# OneSLiPoCharger.net
KiCad netlist of a schematic drawn in EAGLE
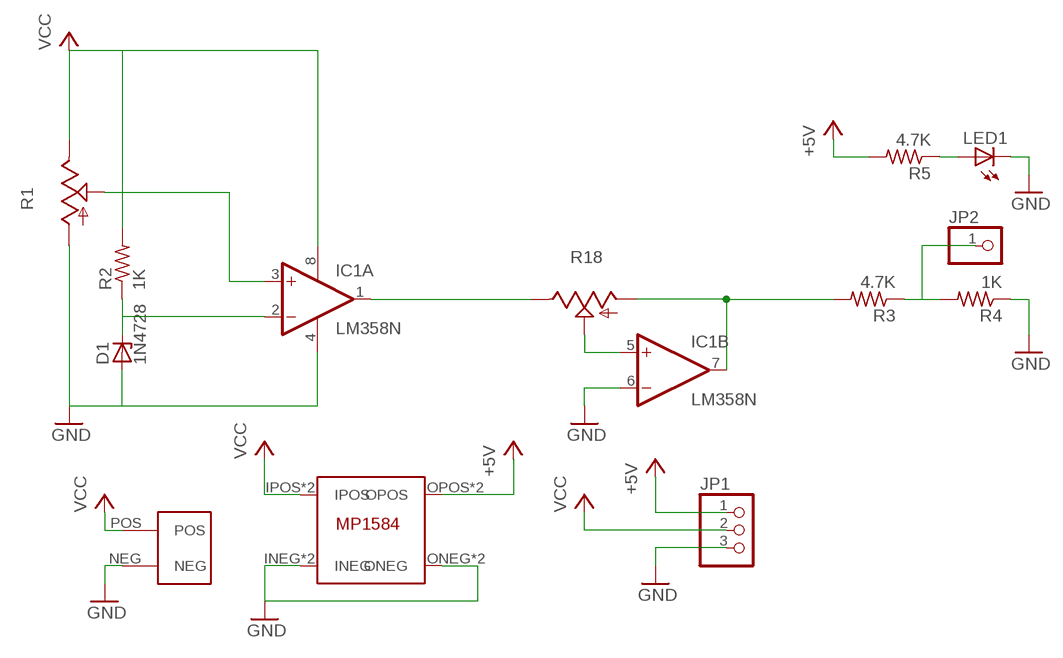
[diagram p0: schematic, sheet 1]
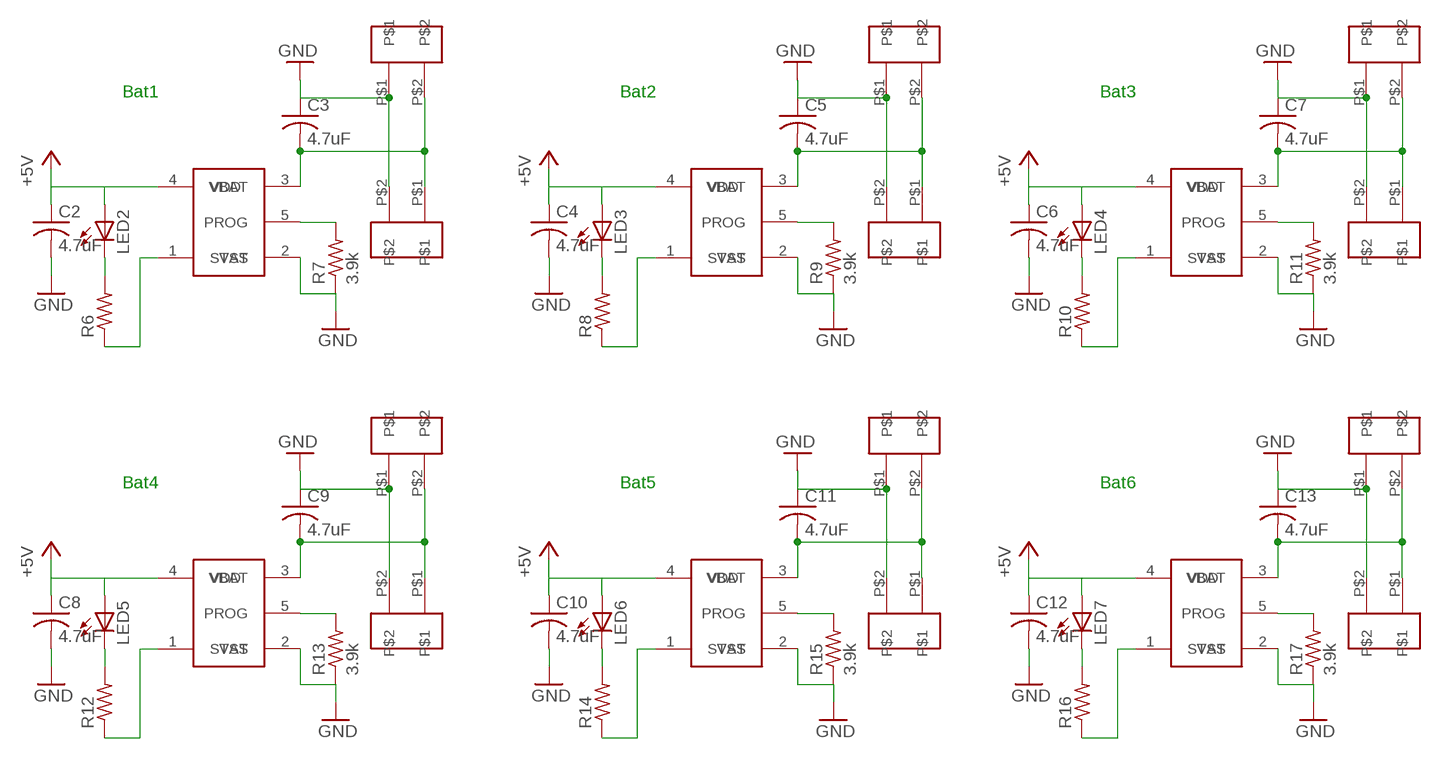
[diagram p1: schematic, sheet 2]

(export (version "E")
  (design (tool "Eeschema 10.0.6"))
  (components
    (comp (ref "C2")
      (value "4.7uF")
      (footprint "eagle-import:C0805")
      (libsource (lib "eagle-import") (part "C-USC0805"))
    )
    (comp (ref "C3")
      (value "4.7uF")
      (footprint "eagle-import:C0805")
      (libsource (lib "eagle-import") (part "C-USC0805"))
    )
    (comp (ref "C4")
      (value "4.7uF")
      (footprint "eagle-import:C0805")
      (libsource (lib "eagle-import") (part "C-USC0805"))
    )
    (comp (ref "C5")
      (value "4.7uF")
      (footprint "eagle-import:C0805")
      (libsource (lib "eagle-import") (part "C-USC0805"))
    )
    (comp (ref "C6")
      (value "4.7uF")
      (footprint "eagle-import:C0805")
      (libsource (lib "eagle-import") (part "C-USC0805"))
    )
    (comp (ref "C7")
      (value "4.7uF")
      (footprint "eagle-import:C0805")
      (libsource (lib "eagle-import") (part "C-USC0805"))
    )
    (comp (ref "C8")
      (value "4.7uF")
      (footprint "eagle-import:C0805")
      (libsource (lib "eagle-import") (part "C-USC0805"))
    )
    (comp (ref "C9")
      (value "4.7uF")
      (footprint "eagle-import:C0805")
      (libsource (lib "eagle-import") (part "C-USC0805"))
    )
    (comp (ref "C10")
      (value "4.7uF")
      (footprint "eagle-import:C0805")
      (libsource (lib "eagle-import") (part "C-USC0805"))
    )
    (comp (ref "C11")
      (value "4.7uF")
      (footprint "eagle-import:C0805")
      (libsource (lib "eagle-import") (part "C-USC0805"))
    )
    (comp (ref "C12")
      (value "4.7uF")
      (footprint "eagle-import:C0805")
      (libsource (lib "eagle-import") (part "C-USC0805"))
    )
    (comp (ref "C13")
      (value "4.7uF")
      (footprint "eagle-import:C0805")
      (libsource (lib "eagle-import") (part "C-USC0805"))
    )
    (comp (ref "LED2")
      (value "LED3MM")
      (footprint "eagle-import:LED3MM")
      (libsource (lib "eagle-import") (part "LED3MM"))
    )
    (comp (ref "LED3")
      (value "LED3MM")
      (footprint "eagle-import:LED3MM")
      (libsource (lib "eagle-import") (part "LED3MM"))
    )
    (comp (ref "LED4")
      (value "LED3MM")
      (footprint "eagle-import:LED3MM")
      (libsource (lib "eagle-import") (part "LED3MM"))
    )
    (comp (ref "LED5")
      (value "LED3MM")
      (footprint "eagle-import:LED3MM")
      (libsource (lib "eagle-import") (part "LED3MM"))
    )
    (comp (ref "LED6")
      (value "LED3MM")
      (footprint "eagle-import:LED3MM")
      (libsource (lib "eagle-import") (part "LED3MM"))
    )
    (comp (ref "LED7")
      (value "LED3MM")
      (footprint "eagle-import:LED3MM")
      (libsource (lib "eagle-import") (part "LED3MM"))
    )
    (comp (ref "R6")
      (value "R-US_M0805")
      (footprint "eagle-import:M0805")
      (libsource (lib "eagle-import") (part "R-US_M0805"))
    )
    (comp (ref "R7")
      (value "3.9k")
      (footprint "eagle-import:M0805")
      (libsource (lib "eagle-import") (part "R-US_M0805"))
    )
    (comp (ref "R8")
      (value "R-US_M0805")
      (footprint "eagle-import:M0805")
      (libsource (lib "eagle-import") (part "R-US_M0805"))
    )
    (comp (ref "R9")
      (value "3.9k")
      (footprint "eagle-import:M0805")
      (libsource (lib "eagle-import") (part "R-US_M0805"))
    )
    (comp (ref "R10")
      (value "R-US_M0805")
      (footprint "eagle-import:M0805")
      (libsource (lib "eagle-import") (part "R-US_M0805"))
    )
    (comp (ref "R11")
      (value "3.9k")
      (footprint "eagle-import:M0805")
      (libsource (lib "eagle-import") (part "R-US_M0805"))
    )
    (comp (ref "R12")
      (value "R-US_M0805")
      (footprint "eagle-import:M0805")
      (libsource (lib "eagle-import") (part "R-US_M0805"))
    )
    (comp (ref "R13")
      (value "3.9k")
      (footprint "eagle-import:M0805")
      (libsource (lib "eagle-import") (part "R-US_M0805"))
    )
    (comp (ref "R14")
      (value "R-US_M0805")
      (footprint "eagle-import:M0805")
      (libsource (lib "eagle-import") (part "R-US_M0805"))
    )
    (comp (ref "R15")
      (value "3.9k")
      (footprint "eagle-import:M0805")
      (libsource (lib "eagle-import") (part "R-US_M0805"))
    )
    (comp (ref "R16")
      (value "R-US_M0805")
      (footprint "eagle-import:M0805")
      (libsource (lib "eagle-import") (part "R-US_M0805"))
    )
    (comp (ref "R17")
      (value "3.9k")
      (footprint "eagle-import:M0805")
      (libsource (lib "eagle-import") (part "R-US_M0805"))
    )
    (comp (ref "U$1")
      (value "MCP73831")
      (footprint "eagle-import:MCP73831-SOT23")
      (libsource (lib "eagle-import") (part "MCP73831"))
    )
    (comp (ref "U$2")
      (value "PICOBLADE-2PIN")
      (footprint "eagle-import:PICOBLADE-2PIN")
      (libsource (lib "eagle-import") (part "PICOBLADE-2PIN"))
    )
    (comp (ref "U$4")
      (value "MCP73831")
      (footprint "eagle-import:MCP73831-SOT23")
      (libsource (lib "eagle-import") (part "MCP73831"))
    )
    (comp (ref "U$5")
      (value "PICOBLADE-2PIN")
      (footprint "eagle-import:PICOBLADE-2PIN")
      (libsource (lib "eagle-import") (part "PICOBLADE-2PIN"))
    )
    (comp (ref "U$6")
      (value "MCP73831")
      (footprint "eagle-import:MCP73831-SOT23")
      (libsource (lib "eagle-import") (part "MCP73831"))
    )
    (comp (ref "U$7")
      (value "PICOBLADE-2PIN")
      (footprint "eagle-import:PICOBLADE-2PIN")
      (libsource (lib "eagle-import") (part "PICOBLADE-2PIN"))
    )
    (comp (ref "U$8")
      (value "MCP73831")
      (footprint "eagle-import:MCP73831-SOT23")
      (libsource (lib "eagle-import") (part "MCP73831"))
    )
    (comp (ref "U$9")
      (value "PICOBLADE-2PIN")
      (footprint "eagle-import:PICOBLADE-2PIN")
      (libsource (lib "eagle-import") (part "PICOBLADE-2PIN"))
    )
    (comp (ref "U$10")
      (value "MCP73831")
      (footprint "eagle-import:MCP73831-SOT23")
      (libsource (lib "eagle-import") (part "MCP73831"))
    )
    (comp (ref "U$11")
      (value "PICOBLADE-2PIN")
      (footprint "eagle-import:PICOBLADE-2PIN")
      (libsource (lib "eagle-import") (part "PICOBLADE-2PIN"))
    )
    (comp (ref "U$12")
      (value "MCP73831")
      (footprint "eagle-import:MCP73831-SOT23")
      (libsource (lib "eagle-import") (part "MCP73831"))
    )
    (comp (ref "U$13")
      (value "PICOBLADE-2PIN")
      (footprint "eagle-import:PICOBLADE-2PIN")
      (libsource (lib "eagle-import") (part "PICOBLADE-2PIN"))
    )
    (comp (ref "U$15")
      (value "JST-PH-2POS")
      (footprint "eagle-import:JST-PH-2POS")
      (libsource (lib "eagle-import") (part "JST-PH-2POS"))
    )
    (comp (ref "U$16")
      (value "JST-PH-2POS")
      (footprint "eagle-import:JST-PH-2POS")
      (libsource (lib "eagle-import") (part "JST-PH-2POS"))
    )
    (comp (ref "U$17")
      (value "JST-PH-2POS")
      (footprint "eagle-import:JST-PH-2POS")
      (libsource (lib "eagle-import") (part "JST-PH-2POS"))
    )
    (comp (ref "U$18")
      (value "JST-PH-2POS")
      (footprint "eagle-import:JST-PH-2POS")
      (libsource (lib "eagle-import") (part "JST-PH-2POS"))
    )
    (comp (ref "U$19")
      (value "JST-PH-2POS")
      (footprint "eagle-import:JST-PH-2POS")
      (libsource (lib "eagle-import") (part "JST-PH-2POS"))
    )
    (comp (ref "U$20")
      (value "JST-PH-2POS")
      (footprint "eagle-import:JST-PH-2POS")
      (libsource (lib "eagle-import") (part "JST-PH-2POS"))
    )
    (comp (ref "D1")
      (value "1N4728")
      (footprint "eagle-import:DO41Z10")
      (libsource (lib "eagle-import") (part "1N4728"))
    )
    (comp (ref "IC1")
      (value "LM358N")
      (footprint "eagle-import:DIL08")
      (libsource (lib "eagle-import") (part "LM358N"))
    )
    (comp (ref "JP1")
      (value "PINHD-1X3")
      (footprint "eagle-import:1X03")
      (libsource (lib "eagle-import") (part "PINHD-1X3"))
    )
    (comp (ref "JP2")
      (value "PINHD-1X1")
      (footprint "eagle-import:1X01")
      (libsource (lib "eagle-import") (part "PINHD-1X1"))
    )
    (comp (ref "LED1")
      (value "LED3MM")
      (footprint "eagle-import:LED3MM")
      (libsource (lib "eagle-import") (part "LED3MM"))
    )
    (comp (ref "R1")
      (value "TRIM_US-B25P")
      (footprint "eagle-import:B25P")
      (libsource (lib "eagle-import") (part "TRIM_US-B25P"))
    )
    (comp (ref "R2")
      (value "1K")
      (footprint "eagle-import:0207_10")
      (libsource (lib "eagle-import") (part "R-US_0207/10"))
    )
    (comp (ref "R3")
      (value "4.7K")
      (footprint "eagle-import:0207_10")
      (libsource (lib "eagle-import") (part "R-US_0207/10"))
    )
    (comp (ref "R4")
      (value "1K")
      (footprint "eagle-import:0207_10")
      (libsource (lib "eagle-import") (part "R-US_0207/10"))
    )
    (comp (ref "R5")
      (value "4.7K")
      (footprint "eagle-import:0207_10")
      (libsource (lib "eagle-import") (part "R-US_0207/10"))
    )
    (comp (ref "R18")
      (value "TRIM_US-B25P")
      (footprint "eagle-import:B25P")
      (libsource (lib "eagle-import") (part "TRIM_US-B25P"))
    )
    (comp (ref "U$3")
      (value "XT60")
      (footprint "eagle-import:XT60")
      (libsource (lib "eagle-import") (part "XT60"))
    )
    (comp (ref "U$14")
      (value "MP1584EN-MOD")
      (footprint "eagle-import:MP1584MOD-TH")
      (libsource (lib "eagle-import") (part "MP1584EN-MOD"))
    )
  )
  (nets
    (net (code "1") (name "+5V") (class "Default")
      (node (ref "C10") (pin "1") (pinfunction "1_1") (pintype "passive"))
      (node (ref "C12") (pin "1") (pinfunction "1_1") (pintype "passive"))
      (node (ref "C2") (pin "1") (pinfunction "1_1") (pintype "passive"))
      (node (ref "C4") (pin "1") (pinfunction "1_1") (pintype "passive"))
      (node (ref "C6") (pin "1") (pinfunction "1_1") (pintype "passive"))
      (node (ref "C8") (pin "1") (pinfunction "1_1") (pintype "passive"))
      (node (ref "JP1") (pin "1") (pinfunction "1_1") (pintype "passive"))
      (node (ref "LED2") (pin "A") (pinfunction "A_A") (pintype "passive"))
      (node (ref "LED3") (pin "A") (pinfunction "A_A") (pintype "passive"))
      (node (ref "LED4") (pin "A") (pinfunction "A_A") (pintype "passive"))
      (node (ref "LED5") (pin "A") (pinfunction "A_A") (pintype "passive"))
      (node (ref "LED6") (pin "A") (pinfunction "A_A") (pintype "passive"))
      (node (ref "LED7") (pin "A") (pinfunction "A_A") (pintype "passive"))
      (node (ref "R5") (pin "2") (pinfunction "2_2") (pintype "passive"))
      (node (ref "U$1") (pin "4") (pinfunction "VDD_4") (pintype "bidirectional"))
      (node (ref "U$10") (pin "4") (pinfunction "VDD_4") (pintype "bidirectional"))
      (node (ref "U$12") (pin "4") (pinfunction "VDD_4") (pintype "bidirectional"))
      (node (ref "U$14") (pin "OPOS") (pinfunction "OPOS_OPOS") (pintype "bidirectional"))
      (node (ref "U$14") (pin "OPOS1") (pinfunction "OPOS_OPOS1") (pintype "bidirectional"))
      (node (ref "U$4") (pin "4") (pinfunction "VDD_4") (pintype "bidirectional"))
      (node (ref "U$6") (pin "4") (pinfunction "VDD_4") (pintype "bidirectional"))
      (node (ref "U$8") (pin "4") (pinfunction "VDD_4") (pintype "bidirectional"))
    )
    (net (code "2") (name "GND") (class "Default")
      (node (ref "C10") (pin "2") (pinfunction "2_2") (pintype "passive"))
      (node (ref "C11") (pin "1") (pinfunction "1_1") (pintype "passive"))
      (node (ref "C12") (pin "2") (pinfunction "2_2") (pintype "passive"))
      (node (ref "C13") (pin "1") (pinfunction "1_1") (pintype "passive"))
      (node (ref "C2") (pin "2") (pinfunction "2_2") (pintype "passive"))
      (node (ref "C3") (pin "1") (pinfunction "1_1") (pintype "passive"))
      (node (ref "C4") (pin "2") (pinfunction "2_2") (pintype "passive"))
      (node (ref "C5") (pin "1") (pinfunction "1_1") (pintype "passive"))
      (node (ref "C6") (pin "2") (pinfunction "2_2") (pintype "passive"))
      (node (ref "C7") (pin "1") (pinfunction "1_1") (pintype "passive"))
      (node (ref "C8") (pin "2") (pinfunction "2_2") (pintype "passive"))
      (node (ref "C9") (pin "1") (pinfunction "1_1") (pintype "passive"))
      (node (ref "D1") (pin "A") (pinfunction "A_A") (pintype "passive"))
      (node (ref "IC1") (pin "4") (pinfunction "V-_4") (pintype "power_in"))
      (node (ref "IC1") (pin "6") (pinfunction "-IN_6") (pintype "input"))
      (node (ref "JP1") (pin "3") (pinfunction "3_3") (pintype "passive"))
      (node (ref "LED1") (pin "K") (pinfunction "C_K") (pintype "passive"))
      (node (ref "R1") (pin "A") (pinfunction "A_A") (pintype "passive"))
      (node (ref "R11") (pin "1") (pinfunction "1_1") (pintype "passive"))
      (node (ref "R13") (pin "1") (pinfunction "1_1") (pintype "passive"))
      (node (ref "R15") (pin "1") (pinfunction "1_1") (pintype "passive"))
      (node (ref "R17") (pin "1") (pinfunction "1_1") (pintype "passive"))
      (node (ref "R4") (pin "1") (pinfunction "1_1") (pintype "passive"))
      (node (ref "R7") (pin "1") (pinfunction "1_1") (pintype "passive"))
      (node (ref "R9") (pin "1") (pinfunction "1_1") (pintype "passive"))
      (node (ref "U$1") (pin "2") (pinfunction "VSS_2") (pintype "bidirectional"))
      (node (ref "U$10") (pin "2") (pinfunction "VSS_2") (pintype "bidirectional"))
      (node (ref "U$11") (pin "P$1") (pinfunction "P$1_P$1") (pintype "bidirectional"))
      (node (ref "U$12") (pin "2") (pinfunction "VSS_2") (pintype "bidirectional"))
      (node (ref "U$13") (pin "P$1") (pinfunction "P$1_P$1") (pintype "bidirectional"))
      (node (ref "U$14") (pin "INEG") (pinfunction "INEG_INEG") (pintype "bidirectional"))
      (node (ref "U$14") (pin "INEG1") (pinfunction "INEG_INEG1") (pintype "bidirectional"))
      (node (ref "U$14") (pin "ONEG") (pinfunction "ONEG_ONEG") (pintype "bidirectional"))
      (node (ref "U$14") (pin "ONEG1") (pinfunction "ONEG_ONEG1") (pintype "bidirectional"))
      (node (ref "U$15") (pin "P$2") (pinfunction "P$2_P$2") (pintype "bidirectional"))
      (node (ref "U$16") (pin "P$2") (pinfunction "P$2_P$2") (pintype "bidirectional"))
      (node (ref "U$17") (pin "P$2") (pinfunction "P$2_P$2") (pintype "bidirectional"))
      (node (ref "U$18") (pin "P$2") (pinfunction "P$2_P$2") (pintype "bidirectional"))
      (node (ref "U$19") (pin "P$2") (pinfunction "P$2_P$2") (pintype "bidirectional"))
      (node (ref "U$2") (pin "P$1") (pinfunction "P$1_P$1") (pintype "bidirectional"))
      (node (ref "U$20") (pin "P$2") (pinfunction "P$2_P$2") (pintype "bidirectional"))
      (node (ref "U$3") (pin "NEG") (pinfunction "NEG_NEG") (pintype "bidirectional"))
      (node (ref "U$4") (pin "2") (pinfunction "VSS_2") (pintype "bidirectional"))
      (node (ref "U$5") (pin "P$1") (pinfunction "P$1_P$1") (pintype "bidirectional"))
      (node (ref "U$6") (pin "2") (pinfunction "VSS_2") (pintype "bidirectional"))
      (node (ref "U$7") (pin "P$1") (pinfunction "P$1_P$1") (pintype "bidirectional"))
      (node (ref "U$8") (pin "2") (pinfunction "VSS_2") (pintype "bidirectional"))
      (node (ref "U$9") (pin "P$1") (pinfunction "P$1_P$1") (pintype "bidirectional"))
    )
    (net (code "3") (name "Net-(IC1A-+IN)") (class "Default")
      (node (ref "IC1") (pin "3") (pinfunction "+IN_3") (pintype "input"))
      (node (ref "R1") (pin "S") (pinfunction "S_S") (pintype "passive"))
    )
    (net (code "4") (name "Net-(IC1A--IN)") (class "Default")
      (node (ref "D1") (pin "C") (pinfunction "C_C") (pintype "passive"))
      (node (ref "IC1") (pin "2") (pinfunction "-IN_2") (pintype "input"))
      (node (ref "R2") (pin "1") (pinfunction "1_1") (pintype "passive"))
    )
    (net (code "5") (name "Net-(IC1A-OUT)") (class "Default")
      (node (ref "IC1") (pin "1") (pinfunction "OUT_1") (pintype "output"))
      (node (ref "R18") (pin "E") (pinfunction "E_E") (pintype "passive"))
    )
    (net (code "6") (name "Net-(IC1B-+IN)") (class "Default")
      (node (ref "IC1") (pin "5") (pinfunction "+IN_5") (pintype "input"))
      (node (ref "R18") (pin "S") (pinfunction "S_S") (pintype "passive"))
    )
    (net (code "7") (name "Net-(IC1B-OUT)") (class "Default")
      (node (ref "IC1") (pin "7") (pinfunction "OUT_7") (pintype "output"))
      (node (ref "R18") (pin "A") (pinfunction "A_A") (pintype "passive"))
      (node (ref "R3") (pin "2") (pinfunction "2_2") (pintype "passive"))
    )
    (net (code "8") (name "Net-(JP2-Pad1)") (class "Default")
      (node (ref "JP2") (pin "1") (pinfunction "1_1") (pintype "passive"))
      (node (ref "R3") (pin "1") (pinfunction "1_1") (pintype "passive"))
      (node (ref "R4") (pin "2") (pinfunction "2_2") (pintype "passive"))
    )
    (net (code "9") (name "Net-(LED1-PadA)") (class "Default")
      (node (ref "LED1") (pin "A") (pinfunction "A_A") (pintype "passive"))
      (node (ref "R5") (pin "1") (pinfunction "1_1") (pintype "passive"))
    )
    (net (code "10") (name "Net-(LED2-C)") (class "Default")
      (node (ref "LED2") (pin "K") (pinfunction "C_K") (pintype "passive"))
      (node (ref "R6") (pin "2") (pinfunction "2_2") (pintype "passive"))
    )
    (net (code "11") (name "Net-(LED3-C)") (class "Default")
      (node (ref "LED3") (pin "K") (pinfunction "C_K") (pintype "passive"))
      (node (ref "R8") (pin "2") (pinfunction "2_2") (pintype "passive"))
    )
    (net (code "12") (name "Net-(LED4-C)") (class "Default")
      (node (ref "LED4") (pin "K") (pinfunction "C_K") (pintype "passive"))
      (node (ref "R10") (pin "2") (pinfunction "2_2") (pintype "passive"))
    )
    (net (code "13") (name "Net-(LED5-C)") (class "Default")
      (node (ref "LED5") (pin "K") (pinfunction "C_K") (pintype "passive"))
      (node (ref "R12") (pin "2") (pinfunction "2_2") (pintype "passive"))
    )
    (net (code "14") (name "Net-(LED6-C)") (class "Default")
      (node (ref "LED6") (pin "K") (pinfunction "C_K") (pintype "passive"))
      (node (ref "R14") (pin "2") (pinfunction "2_2") (pintype "passive"))
    )
    (net (code "15") (name "Net-(LED7-C)") (class "Default")
      (node (ref "LED7") (pin "K") (pinfunction "C_K") (pintype "passive"))
      (node (ref "R16") (pin "2") (pinfunction "2_2") (pintype "passive"))
    )
    (net (code "16") (name "Net-(U$1-PROG)") (class "Default")
      (node (ref "R7") (pin "2") (pinfunction "2_2") (pintype "passive"))
      (node (ref "U$1") (pin "5") (pinfunction "PROG_5") (pintype "bidirectional"))
    )
    (net (code "17") (name "Net-(U$1-STAT)") (class "Default")
      (node (ref "R6") (pin "1") (pinfunction "1_1") (pintype "passive"))
      (node (ref "U$1") (pin "1") (pinfunction "STAT_1") (pintype "bidirectional"))
    )
    (net (code "18") (name "Net-(U$1-VBAT)") (class "Default")
      (node (ref "C3") (pin "2") (pinfunction "2_2") (pintype "passive"))
      (node (ref "U$1") (pin "3") (pinfunction "VBAT_3") (pintype "bidirectional"))
      (node (ref "U$15") (pin "P$1") (pinfunction "P$1_P$1") (pintype "bidirectional"))
      (node (ref "U$2") (pin "P$2") (pinfunction "P$2_P$2") (pintype "bidirectional"))
    )
    (net (code "19") (name "Net-(U$4-PROG)") (class "Default")
      (node (ref "R9") (pin "2") (pinfunction "2_2") (pintype "passive"))
      (node (ref "U$4") (pin "5") (pinfunction "PROG_5") (pintype "bidirectional"))
    )
    (net (code "20") (name "Net-(U$4-STAT)") (class "Default")
      (node (ref "R8") (pin "1") (pinfunction "1_1") (pintype "passive"))
      (node (ref "U$4") (pin "1") (pinfunction "STAT_1") (pintype "bidirectional"))
    )
    (net (code "21") (name "Net-(U$4-VBAT)") (class "Default")
      (node (ref "C5") (pin "2") (pinfunction "2_2") (pintype "passive"))
      (node (ref "U$16") (pin "P$1") (pinfunction "P$1_P$1") (pintype "bidirectional"))
      (node (ref "U$4") (pin "3") (pinfunction "VBAT_3") (pintype "bidirectional"))
      (node (ref "U$5") (pin "P$2") (pinfunction "P$2_P$2") (pintype "bidirectional"))
    )
    (net (code "22") (name "Net-(U$6-PROG)") (class "Default")
      (node (ref "R11") (pin "2") (pinfunction "2_2") (pintype "passive"))
      (node (ref "U$6") (pin "5") (pinfunction "PROG_5") (pintype "bidirectional"))
    )
    (net (code "23") (name "Net-(U$6-STAT)") (class "Default")
      (node (ref "R10") (pin "1") (pinfunction "1_1") (pintype "passive"))
      (node (ref "U$6") (pin "1") (pinfunction "STAT_1") (pintype "bidirectional"))
    )
    (net (code "24") (name "Net-(U$6-VBAT)") (class "Default")
      (node (ref "C7") (pin "2") (pinfunction "2_2") (pintype "passive"))
      (node (ref "U$17") (pin "P$1") (pinfunction "P$1_P$1") (pintype "bidirectional"))
      (node (ref "U$6") (pin "3") (pinfunction "VBAT_3") (pintype "bidirectional"))
      (node (ref "U$7") (pin "P$2") (pinfunction "P$2_P$2") (pintype "bidirectional"))
    )
    (net (code "25") (name "Net-(U$8-PROG)") (class "Default")
      (node (ref "R13") (pin "2") (pinfunction "2_2") (pintype "passive"))
      (node (ref "U$8") (pin "5") (pinfunction "PROG_5") (pintype "bidirectional"))
    )
    (net (code "26") (name "Net-(U$8-STAT)") (class "Default")
      (node (ref "R12") (pin "1") (pinfunction "1_1") (pintype "passive"))
      (node (ref "U$8") (pin "1") (pinfunction "STAT_1") (pintype "bidirectional"))
    )
    (net (code "27") (name "Net-(U$8-VBAT)") (class "Default")
      (node (ref "C9") (pin "2") (pinfunction "2_2") (pintype "passive"))
      (node (ref "U$20") (pin "P$1") (pinfunction "P$1_P$1") (pintype "bidirectional"))
      (node (ref "U$8") (pin "3") (pinfunction "VBAT_3") (pintype "bidirectional"))
      (node (ref "U$9") (pin "P$2") (pinfunction "P$2_P$2") (pintype "bidirectional"))
    )
    (net (code "28") (name "Net-(U$10-PROG)") (class "Default")
      (node (ref "R15") (pin "2") (pinfunction "2_2") (pintype "passive"))
      (node (ref "U$10") (pin "5") (pinfunction "PROG_5") (pintype "bidirectional"))
    )
    (net (code "29") (name "Net-(U$10-STAT)") (class "Default")
      (node (ref "R14") (pin "1") (pinfunction "1_1") (pintype "passive"))
      (node (ref "U$10") (pin "1") (pinfunction "STAT_1") (pintype "bidirectional"))
    )
    (net (code "30") (name "Net-(U$10-VBAT)") (class "Default")
      (node (ref "C11") (pin "2") (pinfunction "2_2") (pintype "passive"))
      (node (ref "U$10") (pin "3") (pinfunction "VBAT_3") (pintype "bidirectional"))
      (node (ref "U$11") (pin "P$2") (pinfunction "P$2_P$2") (pintype "bidirectional"))
      (node (ref "U$19") (pin "P$1") (pinfunction "P$1_P$1") (pintype "bidirectional"))
    )
    (net (code "31") (name "Net-(U$12-PROG)") (class "Default")
      (node (ref "R17") (pin "2") (pinfunction "2_2") (pintype "passive"))
      (node (ref "U$12") (pin "5") (pinfunction "PROG_5") (pintype "bidirectional"))
    )
    (net (code "32") (name "Net-(U$12-STAT)") (class "Default")
      (node (ref "R16") (pin "1") (pinfunction "1_1") (pintype "passive"))
      (node (ref "U$12") (pin "1") (pinfunction "STAT_1") (pintype "bidirectional"))
    )
    (net (code "33") (name "Net-(U$12-VBAT)") (class "Default")
      (node (ref "C13") (pin "2") (pinfunction "2_2") (pintype "passive"))
      (node (ref "U$12") (pin "3") (pinfunction "VBAT_3") (pintype "bidirectional"))
      (node (ref "U$13") (pin "P$2") (pinfunction "P$2_P$2") (pintype "bidirectional"))
      (node (ref "U$18") (pin "P$1") (pinfunction "P$1_P$1") (pintype "bidirectional"))
    )
    (net (code "34") (name "VCC") (class "Default")
      (node (ref "IC1") (pin "8") (pinfunction "V+_8") (pintype "power_in"))
      (node (ref "JP1") (pin "2") (pinfunction "2_2") (pintype "passive"))
      (node (ref "R1") (pin "E") (pinfunction "E_E") (pintype "passive"))
      (node (ref "R2") (pin "2") (pinfunction "2_2") (pintype "passive"))
      (node (ref "U$14") (pin "IPOS") (pinfunction "IPOS_IPOS") (pintype "bidirectional"))
      (node (ref "U$14") (pin "IPOS1") (pinfunction "IPOS_IPOS1") (pintype "bidirectional"))
      (node (ref "U$3") (pin "POS") (pinfunction "POS_POS") (pintype "bidirectional"))
    )
  )
)
